# Arduino_Connexions.net
KiCad netlist of a schematic drawn in EAGLE
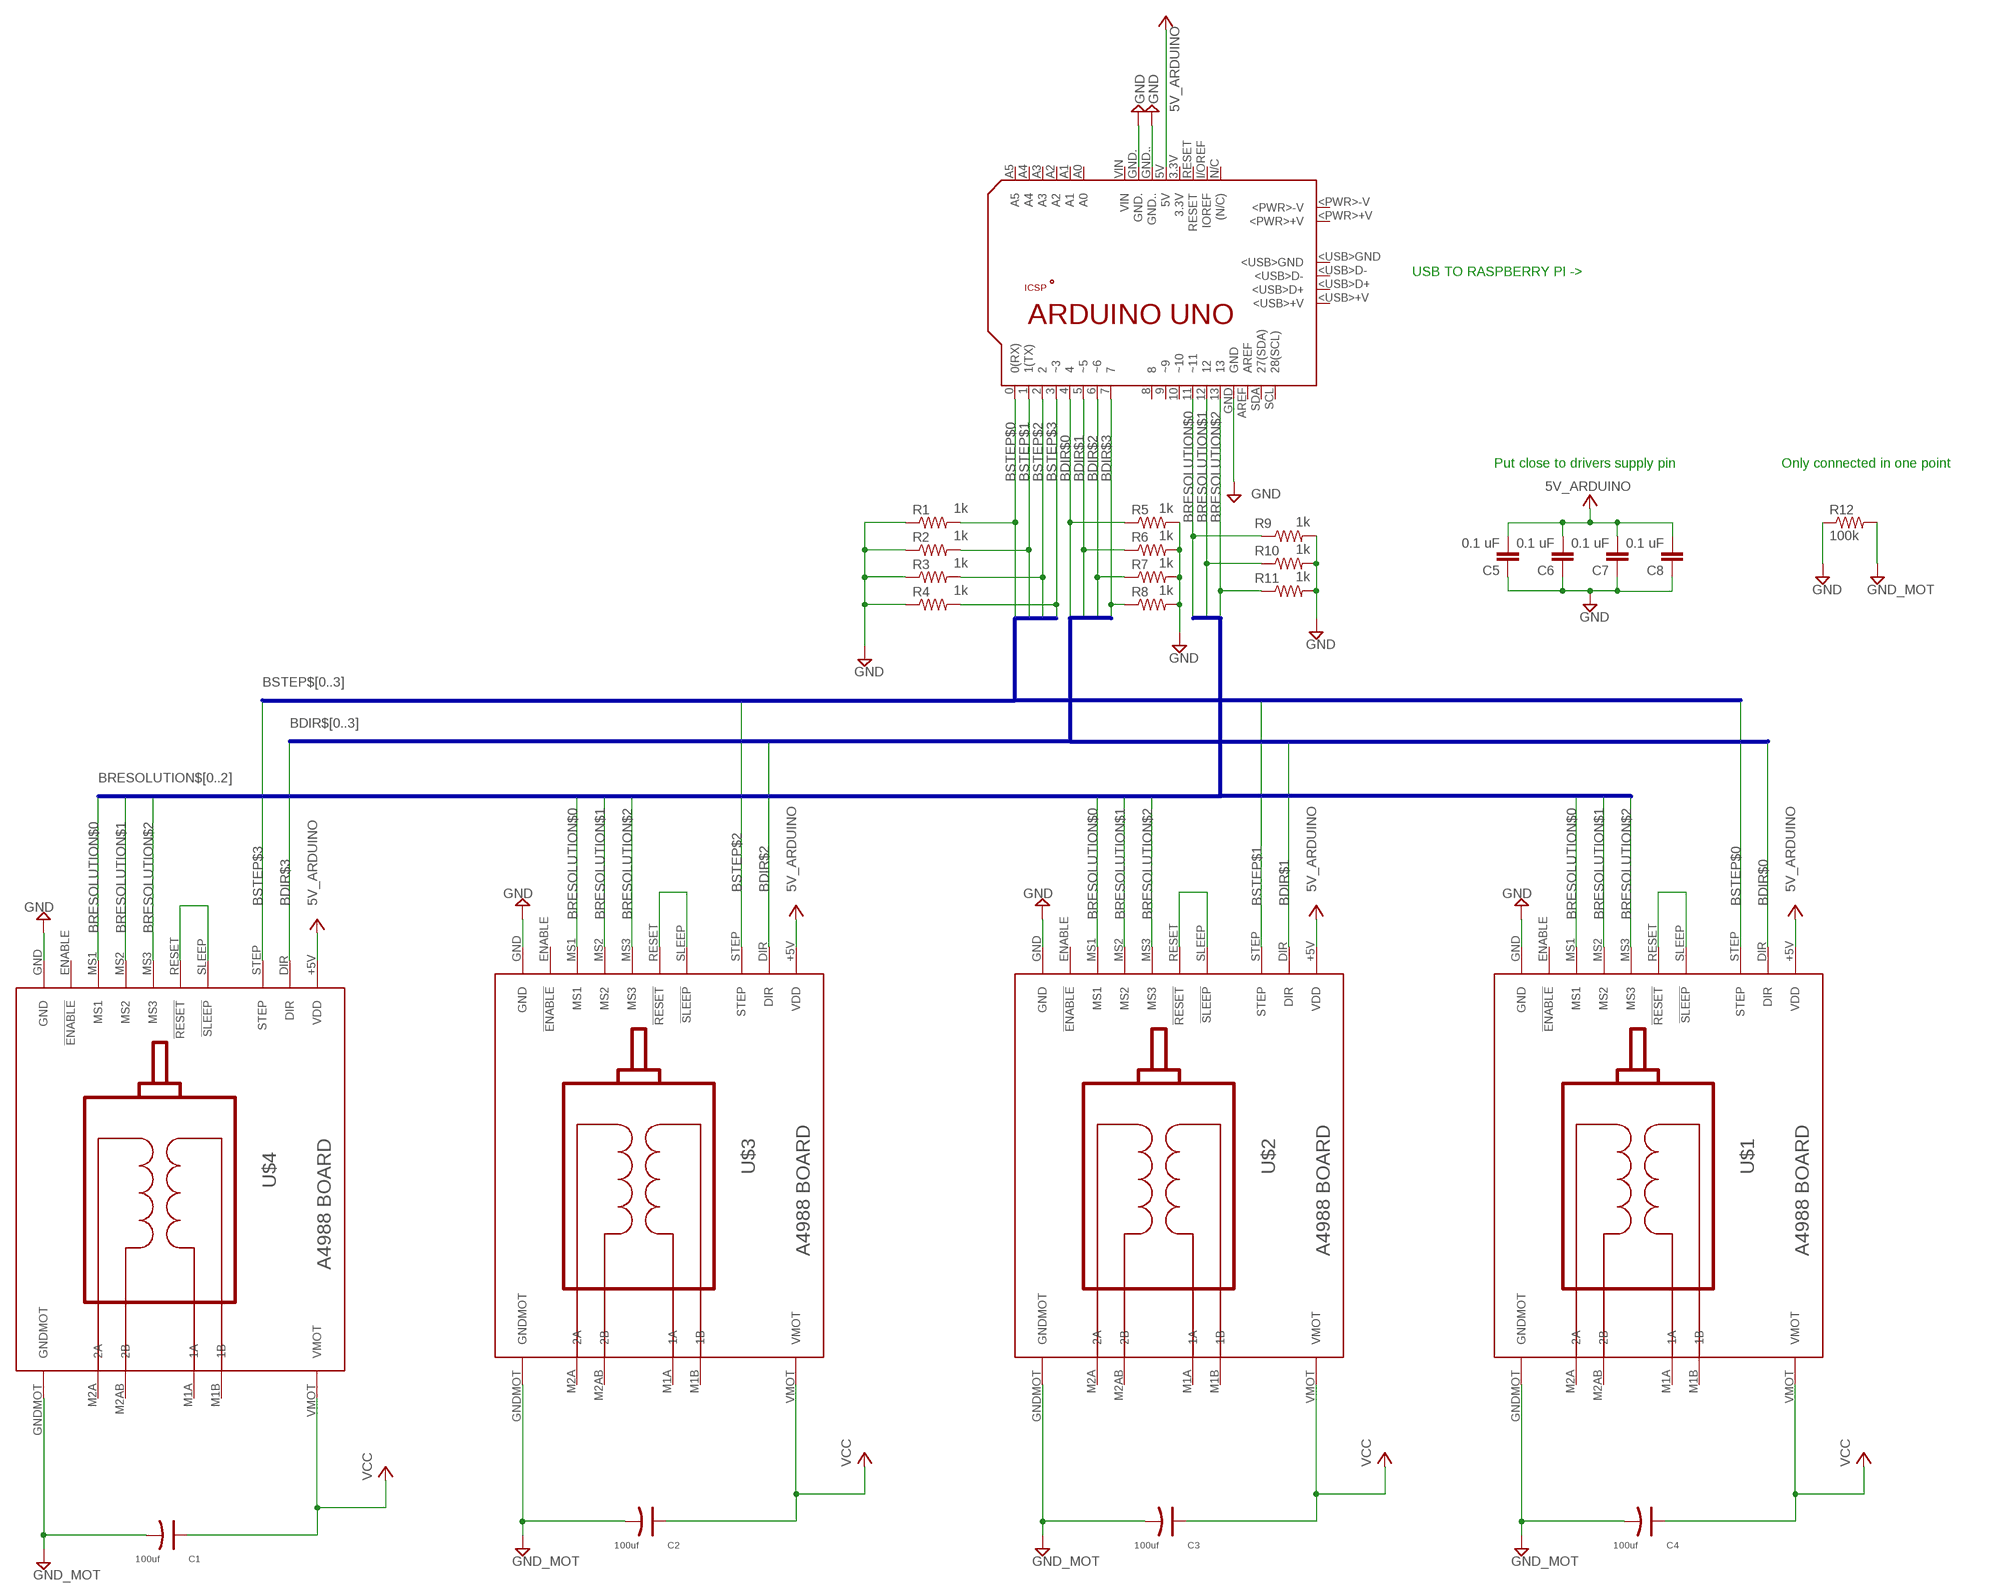
[diagram p0: schematic, sheet 1]

(export (version "E")
  (design (tool "Eeschema 10.0.6"))
  (components
    (comp (ref "C1")
      (value "100uf")
      (footprint "eagle-import:PC-D5.3MM")
      (fields (field (name "MPN") "KS 100uF/16V"))
      (libsource (lib "eagle-import") (part "DIP-ALUMINUM-100UF-16V(D5-H7MM)"))
    )
    (comp (ref "C2")
      (value "100uf")
      (footprint "eagle-import:PC-D5.3MM")
      (fields (field (name "MPN") "KS 100uF/16V"))
      (libsource (lib "eagle-import") (part "DIP-ALUMINUM-100UF-16V(D5-H7MM)"))
    )
    (comp (ref "C3")
      (value "100uf")
      (footprint "eagle-import:PC-D5.3MM")
      (fields (field (name "MPN") "KS 100uF/16V"))
      (libsource (lib "eagle-import") (part "DIP-ALUMINUM-100UF-16V(D5-H7MM)"))
    )
    (comp (ref "C4")
      (value "100uf")
      (footprint "eagle-import:PC-D5.3MM")
      (fields (field (name "MPN") "KS 100uF/16V"))
      (libsource (lib "eagle-import") (part "DIP-ALUMINUM-100UF-16V(D5-H7MM)"))
    )
    (comp (ref "C5")
      (value "0.1 uF")
      (footprint "eagle-import:C025-024X044")
      (libsource (lib "eagle-import") (part "C-EU025-024X044"))
    )
    (comp (ref "C6")
      (value "0.1 uF")
      (footprint "eagle-import:C025-024X044")
      (libsource (lib "eagle-import") (part "C-EU025-024X044"))
    )
    (comp (ref "C7")
      (value "0.1 uF")
      (footprint "eagle-import:C025-024X044")
      (libsource (lib "eagle-import") (part "C-EU025-024X044"))
    )
    (comp (ref "C8")
      (value "0.1 uF")
      (footprint "eagle-import:C025-024X044")
      (libsource (lib "eagle-import") (part "C-EU025-024X044"))
    )
    (comp (ref "PCB2")
      (value "ARDUINO_UNO")
      (footprint "eagle-import:ARDUINO_UNO")
      (libsource (lib "eagle-import") (part "ARDUINO_UNO"))
    )
    (comp (ref "R1")
      (value "1k")
      (footprint "eagle-import:0207_7")
      (libsource (lib "eagle-import") (part "R-US_0207/7"))
    )
    (comp (ref "R2")
      (value "1k")
      (footprint "eagle-import:0207_7")
      (libsource (lib "eagle-import") (part "R-US_0207/7"))
    )
    (comp (ref "R3")
      (value "1k")
      (footprint "eagle-import:0207_7")
      (libsource (lib "eagle-import") (part "R-US_0207/7"))
    )
    (comp (ref "R4")
      (value "1k")
      (footprint "eagle-import:0207_7")
      (libsource (lib "eagle-import") (part "R-US_0207/7"))
    )
    (comp (ref "R5")
      (value "1k")
      (footprint "eagle-import:0207_7")
      (libsource (lib "eagle-import") (part "R-US_0207/7"))
    )
    (comp (ref "R6")
      (value "1k")
      (footprint "eagle-import:0207_7")
      (libsource (lib "eagle-import") (part "R-US_0207/7"))
    )
    (comp (ref "R7")
      (value "1k")
      (footprint "eagle-import:0207_7")
      (libsource (lib "eagle-import") (part "R-US_0207/7"))
    )
    (comp (ref "R8")
      (value "1k")
      (footprint "eagle-import:0207_7")
      (libsource (lib "eagle-import") (part "R-US_0207/7"))
    )
    (comp (ref "R9")
      (value "1k")
      (footprint "eagle-import:0207_7")
      (libsource (lib "eagle-import") (part "R-US_0207/7"))
    )
    (comp (ref "R10")
      (value "1k")
      (footprint "eagle-import:0207_7")
      (libsource (lib "eagle-import") (part "R-US_0207/7"))
    )
    (comp (ref "R11")
      (value "1k")
      (footprint "eagle-import:0207_7")
      (libsource (lib "eagle-import") (part "R-US_0207/7"))
    )
    (comp (ref "R12")
      (value "100k")
      (footprint "eagle-import:0207_7")
      (libsource (lib "eagle-import") (part "R-US_0207/7"))
    )
    (comp (ref "U$1")
      (value "BOARD_A4988")
      (footprint "eagle-import:BOARD_A4988")
      (libsource (lib "eagle-import") (part "BOARD_A4988"))
    )
    (comp (ref "U$2")
      (value "BOARD_A4988")
      (footprint "eagle-import:BOARD_A4988")
      (libsource (lib "eagle-import") (part "BOARD_A4988"))
    )
    (comp (ref "U$3")
      (value "BOARD_A4988")
      (footprint "eagle-import:BOARD_A4988")
      (libsource (lib "eagle-import") (part "BOARD_A4988"))
    )
    (comp (ref "U$4")
      (value "BOARD_A4988")
      (footprint "eagle-import:BOARD_A4988")
      (libsource (lib "eagle-import") (part "BOARD_A4988"))
    )
  )
  (nets
    (net (code "1") (name "/BDIR$0") (class "Default")
      (node (ref "PCB2") (pin "4") (pinfunction "4_4") (pintype "bidirectional"))
      (node (ref "R5") (pin "1") (pinfunction "1_1") (pintype "passive"))
      (node (ref "U$1") (pin "DIR") (pinfunction "DIR_DIR") (pintype "input"))
    )
    (net (code "2") (name "/BDIR$1") (class "Default")
      (node (ref "PCB2") (pin "5") (pinfunction "~{5}_5") (pintype "bidirectional"))
      (node (ref "R6") (pin "1") (pinfunction "1_1") (pintype "passive"))
      (node (ref "U$2") (pin "DIR") (pinfunction "DIR_DIR") (pintype "input"))
    )
    (net (code "3") (name "/BDIR$2") (class "Default")
      (node (ref "PCB2") (pin "6") (pinfunction "~{6}_6") (pintype "bidirectional"))
      (node (ref "R7") (pin "1") (pinfunction "1_1") (pintype "passive"))
      (node (ref "U$3") (pin "DIR") (pinfunction "DIR_DIR") (pintype "input"))
    )
    (net (code "4") (name "/BDIR$3") (class "Default")
      (node (ref "PCB2") (pin "7") (pinfunction "7_7") (pintype "bidirectional"))
      (node (ref "R8") (pin "1") (pinfunction "1_1") (pintype "passive"))
      (node (ref "U$4") (pin "DIR") (pinfunction "DIR_DIR") (pintype "input"))
    )
    (net (code "6") (name "/BRESOLUTION$0") (class "Default")
      (node (ref "PCB2") (pin "11") (pinfunction "~{11}_11") (pintype "bidirectional"))
      (node (ref "R9") (pin "1") (pinfunction "1_1") (pintype "passive"))
      (node (ref "U$1") (pin "MS1") (pinfunction "MS1_MS1") (pintype "input"))
      (node (ref "U$2") (pin "MS1") (pinfunction "MS1_MS1") (pintype "input"))
      (node (ref "U$3") (pin "MS1") (pinfunction "MS1_MS1") (pintype "input"))
      (node (ref "U$4") (pin "MS1") (pinfunction "MS1_MS1") (pintype "input"))
    )
    (net (code "7") (name "/BRESOLUTION$1") (class "Default")
      (node (ref "PCB2") (pin "12") (pinfunction "12_12") (pintype "bidirectional"))
      (node (ref "R10") (pin "1") (pinfunction "1_1") (pintype "passive"))
      (node (ref "U$1") (pin "MS2") (pinfunction "MS2_MS2") (pintype "input"))
      (node (ref "U$2") (pin "MS2") (pinfunction "MS2_MS2") (pintype "input"))
      (node (ref "U$3") (pin "MS2") (pinfunction "MS2_MS2") (pintype "input"))
      (node (ref "U$4") (pin "MS2") (pinfunction "MS2_MS2") (pintype "input"))
    )
    (net (code "8") (name "/BRESOLUTION$2") (class "Default")
      (node (ref "PCB2") (pin "13") (pinfunction "13_13") (pintype "bidirectional"))
      (node (ref "R11") (pin "1") (pinfunction "1_1") (pintype "passive"))
      (node (ref "U$1") (pin "MS3") (pinfunction "MS3_MS3") (pintype "input"))
      (node (ref "U$2") (pin "MS3") (pinfunction "MS3_MS3") (pintype "input"))
      (node (ref "U$3") (pin "MS3") (pinfunction "MS3_MS3") (pintype "input"))
      (node (ref "U$4") (pin "MS3") (pinfunction "MS3_MS3") (pintype "input"))
    )
    (net (code "10") (name "/BSTEP$0") (class "Default")
      (node (ref "PCB2") (pin "0") (pinfunction "0(RX)_0") (pintype "bidirectional"))
      (node (ref "R1") (pin "2") (pinfunction "2_2") (pintype "passive"))
      (node (ref "U$1") (pin "STEP") (pinfunction "STEP_STEP") (pintype "input"))
    )
    (net (code "11") (name "/BSTEP$1") (class "Default")
      (node (ref "PCB2") (pin "1") (pinfunction "1(TX)_1") (pintype "bidirectional"))
      (node (ref "R2") (pin "2") (pinfunction "2_2") (pintype "passive"))
      (node (ref "U$2") (pin "STEP") (pinfunction "STEP_STEP") (pintype "input"))
    )
    (net (code "12") (name "/BSTEP$2") (class "Default")
      (node (ref "PCB2") (pin "2") (pinfunction "2_2") (pintype "bidirectional"))
      (node (ref "R3") (pin "2") (pinfunction "2_2") (pintype "passive"))
      (node (ref "U$3") (pin "STEP") (pinfunction "STEP_STEP") (pintype "input"))
    )
    (net (code "13") (name "/BSTEP$3") (class "Default")
      (node (ref "PCB2") (pin "3") (pinfunction "~{3}_3") (pintype "bidirectional"))
      (node (ref "R4") (pin "2") (pinfunction "2_2") (pintype "passive"))
      (node (ref "U$4") (pin "STEP") (pinfunction "STEP_STEP") (pintype "input"))
    )
    (net (code "15") (name "5V_ARDUINO") (class "Default")
      (node (ref "C1") (pin "+") (pinfunction "+_+") (pintype "passive"))
      (node (ref "C2") (pin "+") (pinfunction "+_+") (pintype "passive"))
      (node (ref "C3") (pin "+") (pinfunction "+_+") (pintype "passive"))
      (node (ref "C4") (pin "+") (pinfunction "+_+") (pintype "passive"))
      (node (ref "C5") (pin "2") (pinfunction "2_2") (pintype "passive"))
      (node (ref "C6") (pin "2") (pinfunction "2_2") (pintype "passive"))
      (node (ref "C7") (pin "2") (pinfunction "2_2") (pintype "passive"))
      (node (ref "C8") (pin "2") (pinfunction "2_2") (pintype "passive"))
      (node (ref "PCB2") (pin "5V") (pinfunction "5V_5V") (pintype "bidirectional"))
      (node (ref "U$1") (pin "+5V") (pinfunction "VDD_+5V") (pintype "power_in"))
      (node (ref "U$1") (pin "VMOT") (pinfunction "VMOT_VMOT") (pintype "power_in"))
      (node (ref "U$2") (pin "+5V") (pinfunction "VDD_+5V") (pintype "power_in"))
      (node (ref "U$2") (pin "VMOT") (pinfunction "VMOT_VMOT") (pintype "power_in"))
      (node (ref "U$3") (pin "+5V") (pinfunction "VDD_+5V") (pintype "power_in"))
      (node (ref "U$3") (pin "VMOT") (pinfunction "VMOT_VMOT") (pintype "power_in"))
      (node (ref "U$4") (pin "+5V") (pinfunction "VDD_+5V") (pintype "power_in"))
      (node (ref "U$4") (pin "VMOT") (pinfunction "VMOT_VMOT") (pintype "power_in"))
    )
    (net (code "16") (name "GND") (class "Default")
      (node (ref "C1") (pin "-") (pinfunction "-_-") (pintype "passive"))
      (node (ref "C2") (pin "-") (pinfunction "-_-") (pintype "passive"))
      (node (ref "C3") (pin "-") (pinfunction "-_-") (pintype "passive"))
      (node (ref "C4") (pin "-") (pinfunction "-_-") (pintype "passive"))
      (node (ref "C5") (pin "1") (pinfunction "1_1") (pintype "passive"))
      (node (ref "C6") (pin "1") (pinfunction "1_1") (pintype "passive"))
      (node (ref "C7") (pin "1") (pinfunction "1_1") (pintype "passive"))
      (node (ref "C8") (pin "1") (pinfunction "1_1") (pintype "passive"))
      (node (ref "PCB2") (pin "GND") (pinfunction "GND_GND") (pintype "bidirectional"))
      (node (ref "PCB2") (pin "GND.") (pinfunction "GND._GND.") (pintype "bidirectional"))
      (node (ref "PCB2") (pin "GND..") (pinfunction "GND.._GND..") (pintype "bidirectional"))
      (node (ref "R1") (pin "1") (pinfunction "1_1") (pintype "passive"))
      (node (ref "R10") (pin "2") (pinfunction "2_2") (pintype "passive"))
      (node (ref "R11") (pin "2") (pinfunction "2_2") (pintype "passive"))
      (node (ref "R12") (pin "1") (pinfunction "1_1") (pintype "passive"))
      (node (ref "R12") (pin "2") (pinfunction "2_2") (pintype "passive"))
      (node (ref "R2") (pin "1") (pinfunction "1_1") (pintype "passive"))
      (node (ref "R3") (pin "1") (pinfunction "1_1") (pintype "passive"))
      (node (ref "R4") (pin "1") (pinfunction "1_1") (pintype "passive"))
      (node (ref "R5") (pin "2") (pinfunction "2_2") (pintype "passive"))
      (node (ref "R6") (pin "2") (pinfunction "2_2") (pintype "passive"))
      (node (ref "R7") (pin "2") (pinfunction "2_2") (pintype "passive"))
      (node (ref "R8") (pin "2") (pinfunction "2_2") (pintype "passive"))
      (node (ref "R9") (pin "2") (pinfunction "2_2") (pintype "passive"))
      (node (ref "U$1") (pin "GND") (pinfunction "GND_GND") (pintype "power_in"))
      (node (ref "U$1") (pin "GNDMOT") (pinfunction "GNDMOT_GNDMOT") (pintype "power_in"))
      (node (ref "U$2") (pin "GND") (pinfunction "GND_GND") (pintype "power_in"))
      (node (ref "U$2") (pin "GNDMOT") (pinfunction "GNDMOT_GNDMOT") (pintype "power_in"))
      (node (ref "U$3") (pin "GND") (pinfunction "GND_GND") (pintype "power_in"))
      (node (ref "U$3") (pin "GNDMOT") (pinfunction "GNDMOT_GNDMOT") (pintype "power_in"))
      (node (ref "U$4") (pin "GND") (pinfunction "GND_GND") (pintype "power_in"))
      (node (ref "U$4") (pin "GNDMOT") (pinfunction "GNDMOT_GNDMOT") (pintype "power_in"))
    )
    (net (code "17") (name "Net-(U$1-~{RESET})") (class "Default")
      (node (ref "U$1") (pin "RESET") (pinfunction "~{RESET}_RESET") (pintype "input"))
      (node (ref "U$1") (pin "SLEEP") (pinfunction "~{SLEEP}_SLEEP") (pintype "input"))
    )
    (net (code "18") (name "Net-(U$2-~{RESET})") (class "Default")
      (node (ref "U$2") (pin "RESET") (pinfunction "~{RESET}_RESET") (pintype "input"))
      (node (ref "U$2") (pin "SLEEP") (pinfunction "~{SLEEP}_SLEEP") (pintype "input"))
    )
    (net (code "19") (name "Net-(U$3-~{RESET})") (class "Default")
      (node (ref "U$3") (pin "RESET") (pinfunction "~{RESET}_RESET") (pintype "input"))
      (node (ref "U$3") (pin "SLEEP") (pinfunction "~{SLEEP}_SLEEP") (pintype "input"))
    )
    (net (code "20") (name "Net-(U$4-~{RESET})") (class "Default")
      (node (ref "U$4") (pin "RESET") (pinfunction "~{RESET}_RESET") (pintype "input"))
      (node (ref "U$4") (pin "SLEEP") (pinfunction "~{SLEEP}_SLEEP") (pintype "input"))
    )
    (net (code "21") (name "unconnected-(PCB2-(N{slash}C)-PadN{slash}C)") (class "Default")
      (node (ref "PCB2") (pin "N/C") (pinfunction "(N/C)_N/C") (pintype "bidirectional"))
    )
    (net (code "22") (name "unconnected-(PCB2-27(SDA)-PadSDA)") (class "Default")
      (node (ref "PCB2") (pin "SDA") (pinfunction "27(SDA)_SDA") (pintype "bidirectional"))
    )
    (net (code "23") (name "unconnected-(PCB2-28(SCL)-PadSCL)") (class "Default")
      (node (ref "PCB2") (pin "SCL") (pinfunction "28(SCL)_SCL") (pintype "bidirectional"))
    )
    (net (code "24") (name "unconnected-(PCB2-IOREF-PadI{slash}OREF)") (class "Default")
      (node (ref "PCB2") (pin "I/OREF") (pinfunction "IOREF_I/OREF") (pintype "bidirectional"))
    )
    (net (code "25") (name "unconnected-(PCB2-Pad+5V)") (class "Default")
      (node (ref "PCB2") (pin "+5V") (pinfunction "+5V_+5V") (pintype "bidirectional"))
    )
    (net (code "26") (name "unconnected-(PCB2-Pad3.3V)") (class "Default")
      (node (ref "PCB2") (pin "3.3V") (pinfunction "3.3V_3.3V") (pintype "bidirectional"))
    )
    (net (code "27") (name "unconnected-(PCB2-Pad8)") (class "Default")
      (node (ref "PCB2") (pin "8") (pinfunction "8_8") (pintype "bidirectional"))
    )
    (net (code "28") (name "unconnected-(PCB2-Pad<PWR>+V)") (class "Default")
      (node (ref "PCB2") (pin "<PWR>+V") (pinfunction "<PWR>+V_<PWR>+V") (pintype "bidirectional"))
    )
    (net (code "29") (name "unconnected-(PCB2-Pad<PWR>-V)") (class "Default")
      (node (ref "PCB2") (pin "<PWR>-V") (pinfunction "<PWR>-V_<PWR>-V") (pintype "bidirectional"))
    )
    (net (code "30") (name "unconnected-(PCB2-Pad<USB>+V)") (class "Default")
      (node (ref "PCB2") (pin "<USB>+V") (pinfunction "<USB>+V_<USB>+V") (pintype "bidirectional"))
    )
    (net (code "31") (name "unconnected-(PCB2-Pad<USB>D+)") (class "Default")
      (node (ref "PCB2") (pin "<USB>D+") (pinfunction "<USB>D+_<USB>D+") (pintype "bidirectional"))
    )
    (net (code "32") (name "unconnected-(PCB2-Pad<USB>D-)") (class "Default")
      (node (ref "PCB2") (pin "<USB>D-") (pinfunction "<USB>D-_<USB>D-") (pintype "bidirectional"))
    )
    (net (code "33") (name "unconnected-(PCB2-Pad<USB>GND)") (class "Default")
      (node (ref "PCB2") (pin "<USB>GND") (pinfunction "<USB>GND_<USB>GND") (pintype "bidirectional"))
    )
    (net (code "34") (name "unconnected-(PCB2-PadA0)") (class "Default")
      (node (ref "PCB2") (pin "A0") (pinfunction "A0_A0") (pintype "bidirectional"))
    )
    (net (code "35") (name "unconnected-(PCB2-PadA1)") (class "Default")
      (node (ref "PCB2") (pin "A1") (pinfunction "A1_A1") (pintype "bidirectional"))
    )
    (net (code "36") (name "unconnected-(PCB2-PadA2)") (class "Default")
      (node (ref "PCB2") (pin "A2") (pinfunction "A2_A2") (pintype "bidirectional"))
    )
    (net (code "37") (name "unconnected-(PCB2-PadA3)") (class "Default")
      (node (ref "PCB2") (pin "A3") (pinfunction "A3_A3") (pintype "bidirectional"))
    )
    (net (code "38") (name "unconnected-(PCB2-PadA4)") (class "Default")
      (node (ref "PCB2") (pin "A4") (pinfunction "A4_A4") (pintype "bidirectional"))
    )
    (net (code "39") (name "unconnected-(PCB2-PadA5)") (class "Default")
      (node (ref "PCB2") (pin "A5") (pinfunction "A5_A5") (pintype "bidirectional"))
    )
    (net (code "40") (name "unconnected-(PCB2-PadAREF)") (class "Default")
      (node (ref "PCB2") (pin "AREF") (pinfunction "AREF_AREF") (pintype "bidirectional"))
    )
    (net (code "41") (name "unconnected-(PCB2-PadGND_)") (class "Default")
      (node (ref "PCB2") (pin "GND_") (pinfunction "GND__GND_") (pintype "bidirectional"))
    )
    (net (code "42") (name "unconnected-(PCB2-PadMISO)") (class "Default")
      (node (ref "PCB2") (pin "MISO") (pinfunction "MISO_MISO") (pintype "bidirectional"))
    )
    (net (code "43") (name "unconnected-(PCB2-PadMOSI)") (class "Default")
      (node (ref "PCB2") (pin "MOSI") (pinfunction "MOSI_MOSI") (pintype "bidirectional"))
    )
    (net (code "44") (name "unconnected-(PCB2-PadRESET)") (class "Default")
      (node (ref "PCB2") (pin "RESET") (pinfunction "RESET_RESET") (pintype "bidirectional"))
    )
    (net (code "45") (name "unconnected-(PCB2-PadRESET.)") (class "Default")
      (node (ref "PCB2") (pin "RESET.") (pinfunction "RESET._RESET.") (pintype "bidirectional"))
    )
    (net (code "46") (name "unconnected-(PCB2-PadSCK)") (class "Default")
      (node (ref "PCB2") (pin "SCK") (pinfunction "SCK_SCK") (pintype "bidirectional"))
    )
    (net (code "47") (name "unconnected-(PCB2-PadVIN)") (class "Default")
      (node (ref "PCB2") (pin "VIN") (pinfunction "VIN_VIN") (pintype "bidirectional"))
    )
    (net (code "48") (name "unconnected-(PCB2-~{9}-Pad9)") (class "Default")
      (node (ref "PCB2") (pin "9") (pinfunction "~{9}_9") (pintype "bidirectional"))
    )
    (net (code "49") (name "unconnected-(PCB2-~{10}-Pad10)") (class "Default")
      (node (ref "PCB2") (pin "10") (pinfunction "~{10}_10") (pintype "bidirectional"))
    )
    (net (code "50") (name "unconnected-(U$1-1A-PadM1A)") (class "Default")
      (node (ref "U$1") (pin "M1A") (pinfunction "1A_M1A") (pintype "output"))
    )
    (net (code "51") (name "unconnected-(U$1-1B-PadM1B)") (class "Default")
      (node (ref "U$1") (pin "M1B") (pinfunction "1B_M1B") (pintype "output"))
    )
    (net (code "52") (name "unconnected-(U$1-2A-PadM2A)") (class "Default")
      (node (ref "U$1") (pin "M2A") (pinfunction "2A_M2A") (pintype "output"))
    )
    (net (code "53") (name "unconnected-(U$1-2B-PadM2AB)") (class "Default")
      (node (ref "U$1") (pin "M2AB") (pinfunction "2B_M2AB") (pintype "output"))
    )
    (net (code "54") (name "unconnected-(U$1-~{ENABLE}-PadENABLE)") (class "Default")
      (node (ref "U$1") (pin "ENABLE") (pinfunction "~{ENABLE}_ENABLE") (pintype "input"))
    )
    (net (code "55") (name "unconnected-(U$2-1A-PadM1A)") (class "Default")
      (node (ref "U$2") (pin "M1A") (pinfunction "1A_M1A") (pintype "output"))
    )
    (net (code "56") (name "unconnected-(U$2-1B-PadM1B)") (class "Default")
      (node (ref "U$2") (pin "M1B") (pinfunction "1B_M1B") (pintype "output"))
    )
    (net (code "57") (name "unconnected-(U$2-2A-PadM2A)") (class "Default")
      (node (ref "U$2") (pin "M2A") (pinfunction "2A_M2A") (pintype "output"))
    )
    (net (code "58") (name "unconnected-(U$2-2B-PadM2AB)") (class "Default")
      (node (ref "U$2") (pin "M2AB") (pinfunction "2B_M2AB") (pintype "output"))
    )
    (net (code "59") (name "unconnected-(U$2-~{ENABLE}-PadENABLE)") (class "Default")
      (node (ref "U$2") (pin "ENABLE") (pinfunction "~{ENABLE}_ENABLE") (pintype "input"))
    )
    (net (code "60") (name "unconnected-(U$3-1A-PadM1A)") (class "Default")
      (node (ref "U$3") (pin "M1A") (pinfunction "1A_M1A") (pintype "output"))
    )
    (net (code "61") (name "unconnected-(U$3-1B-PadM1B)") (class "Default")
      (node (ref "U$3") (pin "M1B") (pinfunction "1B_M1B") (pintype "output"))
    )
    (net (code "62") (name "unconnected-(U$3-2A-PadM2A)") (class "Default")
      (node (ref "U$3") (pin "M2A") (pinfunction "2A_M2A") (pintype "output"))
    )
    (net (code "63") (name "unconnected-(U$3-2B-PadM2AB)") (class "Default")
      (node (ref "U$3") (pin "M2AB") (pinfunction "2B_M2AB") (pintype "output"))
    )
    (net (code "64") (name "unconnected-(U$3-~{ENABLE}-PadENABLE)") (class "Default")
      (node (ref "U$3") (pin "ENABLE") (pinfunction "~{ENABLE}_ENABLE") (pintype "input"))
    )
    (net (code "65") (name "unconnected-(U$4-1A-PadM1A)") (class "Default")
      (node (ref "U$4") (pin "M1A") (pinfunction "1A_M1A") (pintype "output"))
    )
    (net (code "66") (name "unconnected-(U$4-1B-PadM1B)") (class "Default")
      (node (ref "U$4") (pin "M1B") (pinfunction "1B_M1B") (pintype "output"))
    )
    (net (code "67") (name "unconnected-(U$4-2A-PadM2A)") (class "Default")
      (node (ref "U$4") (pin "M2A") (pinfunction "2A_M2A") (pintype "output"))
    )
    (net (code "68") (name "unconnected-(U$4-2B-PadM2AB)") (class "Default")
      (node (ref "U$4") (pin "M2AB") (pinfunction "2B_M2AB") (pintype "output"))
    )
    (net (code "69") (name "unconnected-(U$4-~{ENABLE}-PadENABLE)") (class "Default")
      (node (ref "U$4") (pin "ENABLE") (pinfunction "~{ENABLE}_ENABLE") (pintype "input"))
    )
  )
)
